# STEP_MOTOR_DRIVER_2.net
KiCad netlist of a schematic drawn in Altium Designer
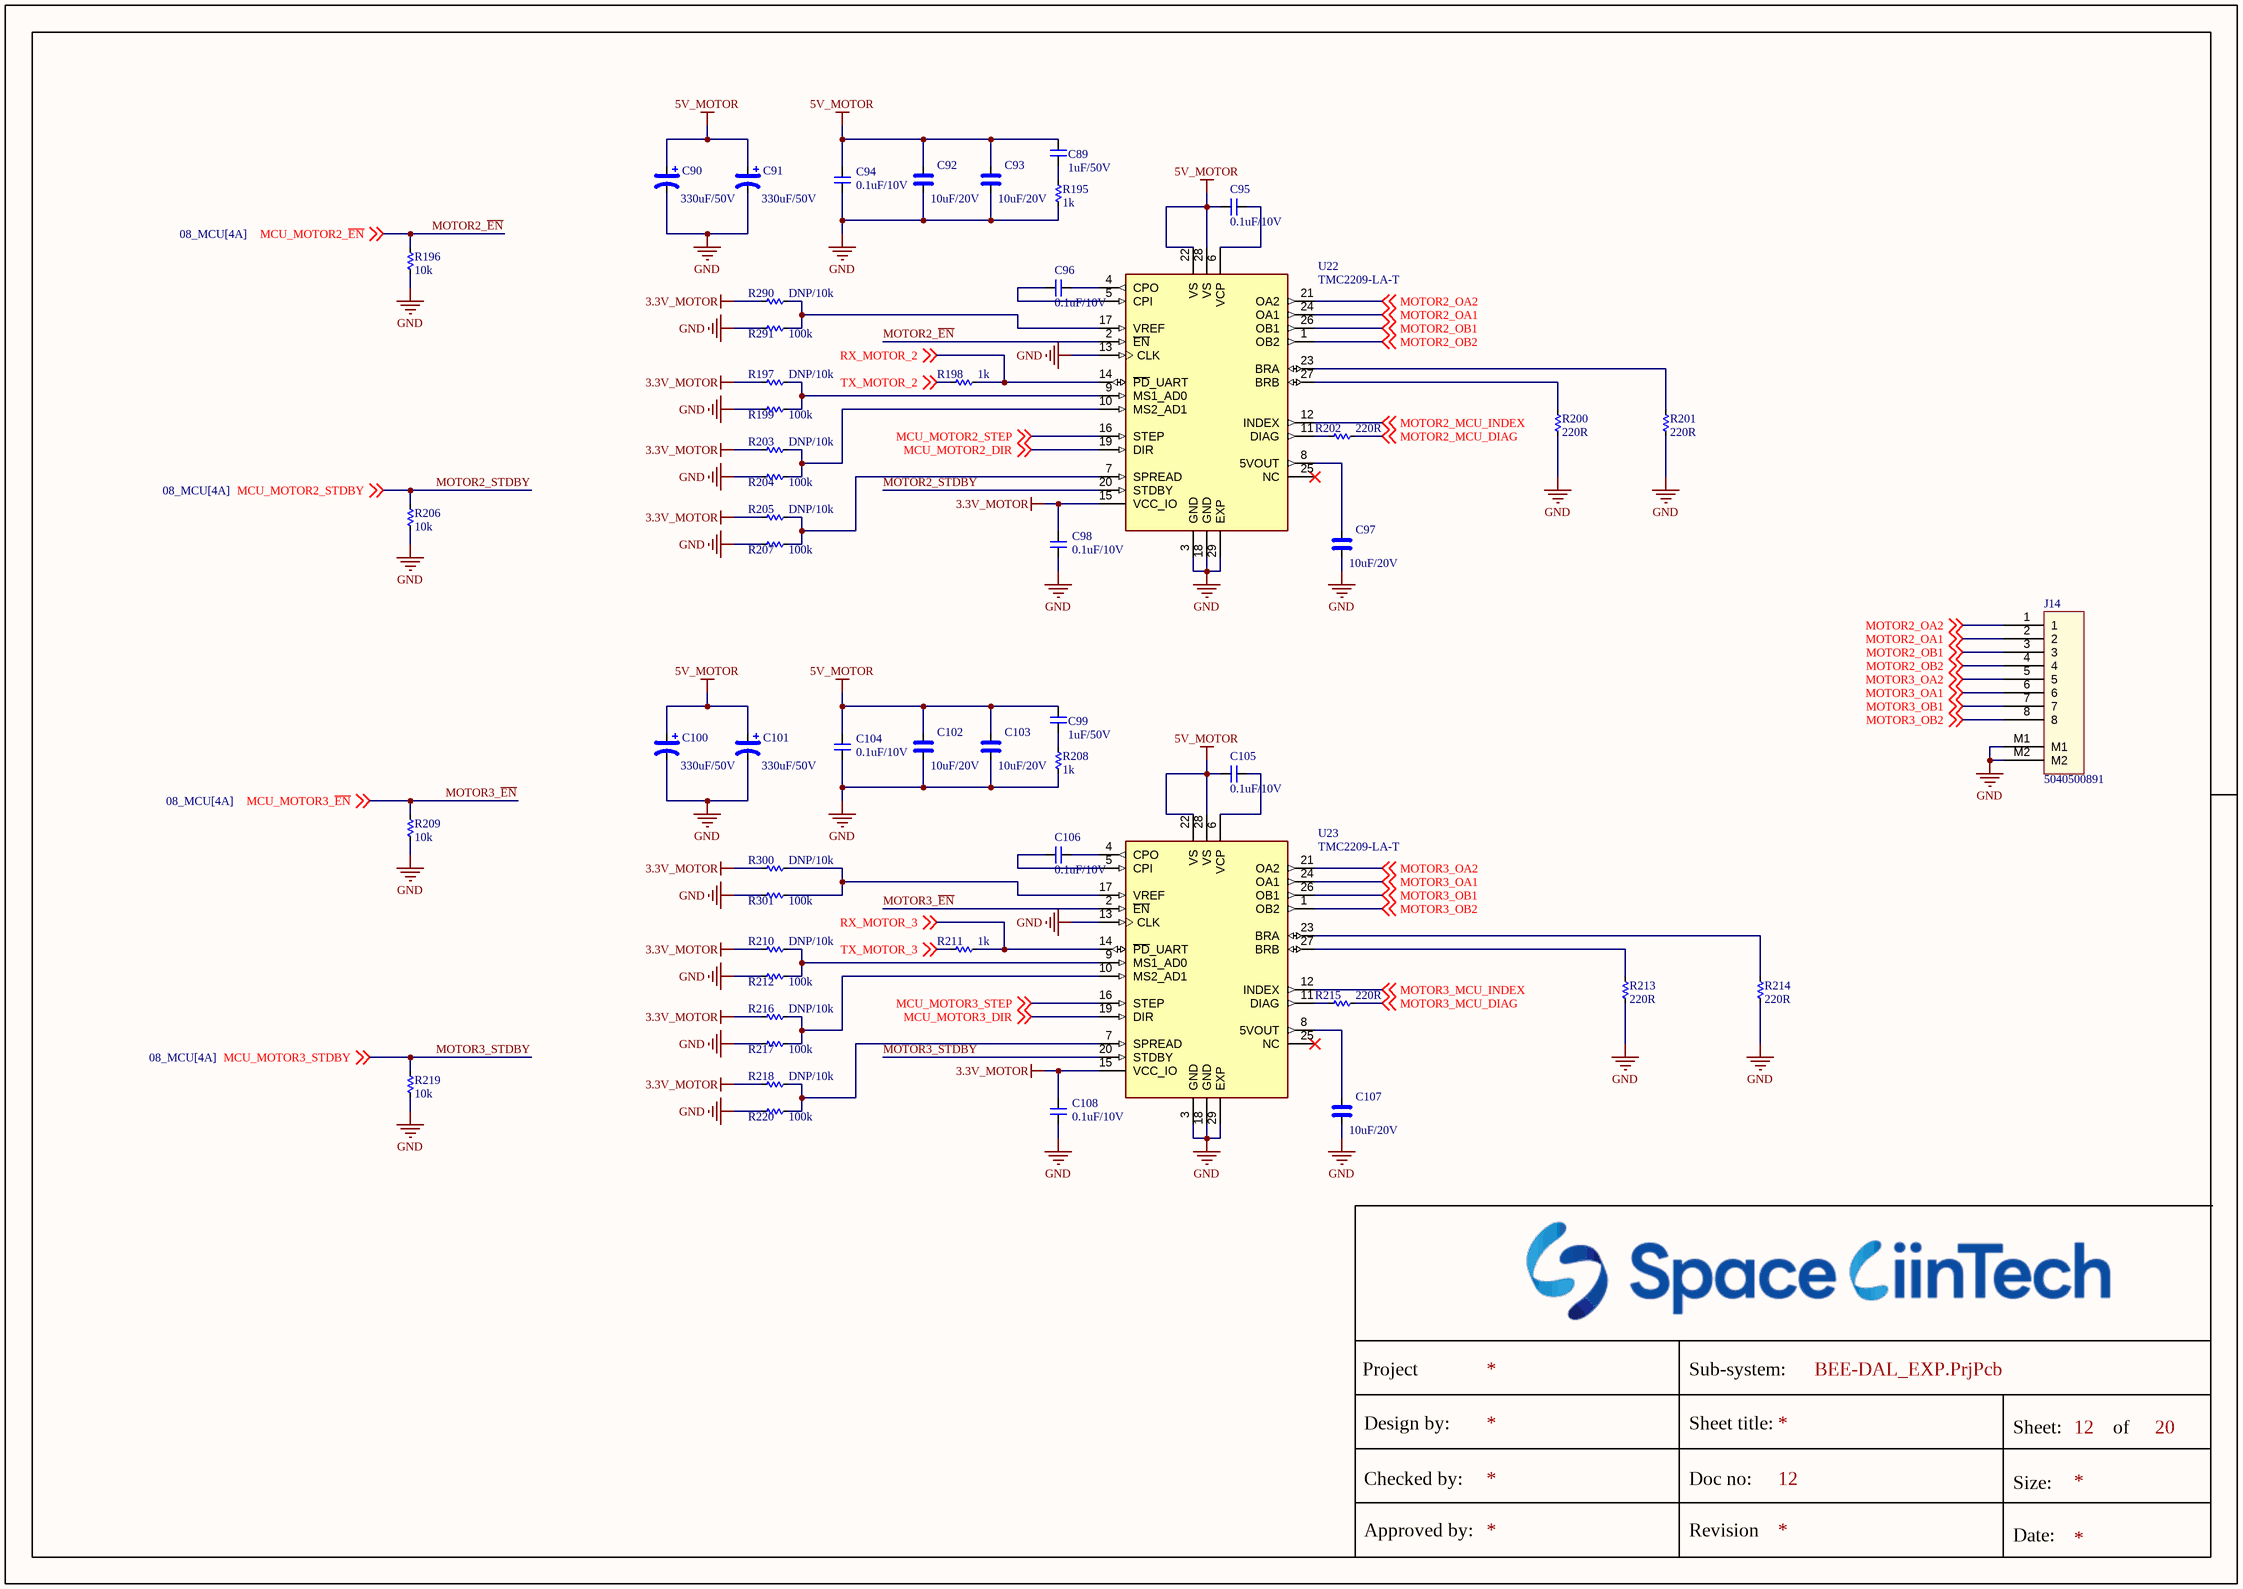
[diagram p0: STEP_MOTOR_DRIVER_2.SchDoc]

(export (version "E")
  (design (tool "Eeschema 10.0.6"))
  (components
    (comp (ref "C89")
      (value "1uF/50V")
      (footprint "CAP_C_1005X50_L")
      (description "CAP")
      (libsource (lib "LABLIB") (part "_CAP_C_2"))
    )
    (comp (ref "C90")
      (value "330uF/50V")
      (footprint "CAP_MP_3216X180")
      (description "CAP Polarization High Value")
      (libsource (lib "LABLIB") (part "_CAP_Pola_High_2"))
    )
    (comp (ref "C91")
      (value "330uF/50V")
      (footprint "CAP_MP_3216X180")
      (description "CAP Polarization High Value")
      (libsource (lib "LABLIB") (part "_CAP_Pola_High_2"))
    )
    (comp (ref "C92")
      (value "10uF/20V")
      (footprint "CAP_C_2012X110")
      (description "CAP High Value")
      (libsource (lib "LABLIB") (part "_CAP_C_High_2"))
    )
    (comp (ref "C93")
      (value "10uF/20V")
      (footprint "CAP_C_2012X110")
      (description "CAP High Value")
      (libsource (lib "LABLIB") (part "_CAP_C_High_2"))
    )
    (comp (ref "C94")
      (value "0.1uF/10V")
      (footprint "CAP_C_1005X50_L")
      (description "CAP")
      (libsource (lib "LABLIB") (part "_CAP_C_2"))
    )
    (comp (ref "C95")
      (value "0.1uF/10V")
      (footprint "CAP_C_1005X50_L")
      (description "CAP")
      (libsource (lib "LABLIB") (part "_CAP_C_2"))
    )
    (comp (ref "C96")
      (value "0.1uF/10V")
      (footprint "CAP_C_1005X50_L")
      (description "CAP")
      (libsource (lib "LABLIB") (part "_CAP_C_2"))
    )
    (comp (ref "C97")
      (value "10uF/20V")
      (footprint "CAP_C_2012X110")
      (description "CAP High Value")
      (libsource (lib "LABLIB") (part "_CAP_C_High_2"))
    )
    (comp (ref "C98")
      (value "0.1uF/10V")
      (footprint "CAP_C_1005X50_L")
      (description "CAP")
      (libsource (lib "LABLIB") (part "_CAP_C_2"))
    )
    (comp (ref "C99")
      (value "1uF/50V")
      (footprint "CAP_C_1005X50_L")
      (description "CAP")
      (libsource (lib "LABLIB") (part "_CAP_C_2"))
    )
    (comp (ref "C100")
      (value "330uF/50V")
      (footprint "CAP_MP_3216X180")
      (description "CAP Polarization High Value")
      (libsource (lib "LABLIB") (part "_CAP_Pola_High_2"))
    )
    (comp (ref "C101")
      (value "330uF/50V")
      (footprint "CAP_MP_3216X180")
      (description "CAP Polarization High Value")
      (libsource (lib "LABLIB") (part "_CAP_Pola_High_2"))
    )
    (comp (ref "C102")
      (value "10uF/20V")
      (footprint "CAP_C_2012X110")
      (description "CAP High Value")
      (libsource (lib "LABLIB") (part "_CAP_C_High_2"))
    )
    (comp (ref "C103")
      (value "10uF/20V")
      (footprint "CAP_C_2012X110")
      (description "CAP High Value")
      (libsource (lib "LABLIB") (part "_CAP_C_High_2"))
    )
    (comp (ref "C104")
      (value "0.1uF/10V")
      (footprint "CAP_C_1005X50_L")
      (description "CAP")
      (libsource (lib "LABLIB") (part "_CAP_C_2"))
    )
    (comp (ref "C105")
      (value "0.1uF/10V")
      (footprint "CAP_C_1005X50_L")
      (description "CAP")
      (libsource (lib "LABLIB") (part "_CAP_C_2"))
    )
    (comp (ref "C106")
      (value "0.1uF/10V")
      (footprint "CAP_C_1005X50_L")
      (description "CAP")
      (libsource (lib "LABLIB") (part "_CAP_C_2"))
    )
    (comp (ref "C107")
      (value "10uF/20V")
      (footprint "CAP_C_2012X110")
      (description "CAP High Value")
      (libsource (lib "LABLIB") (part "_CAP_C_High_2"))
    )
    (comp (ref "C108")
      (value "0.1uF/10V")
      (footprint "CAP_C_1005X50_L")
      (description "CAP")
      (libsource (lib "LABLIB") (part "_CAP_C_2"))
    )
    (comp (ref "J14")
      (value "5040500891")
      (footprint "MOLEX_5040500891")
      (libsource (lib "LABLIB") (part "Header 8x1_2M"))
    )
    (comp (ref "R195")
      (value "1k")
      (footprint "RES_C_1005X40")
      (description "RES")
      (libsource (lib "LABLIB") (part "_RES_B_2"))
    )
    (comp (ref "R196")
      (value "10k")
      (footprint "RES_C_1005X40")
      (description "RES")
      (libsource (lib "LABLIB") (part "_RES_B_2"))
    )
    (comp (ref "R197")
      (value "DNP/10k")
      (footprint "RES_C_1005X40")
      (description "RES")
      (libsource (lib "LABLIB") (part "_RES_B_2"))
    )
    (comp (ref "R198")
      (value "1k")
      (footprint "RES_C_1005X40")
      (description "RES")
      (libsource (lib "LABLIB") (part "_RES_B_2"))
    )
    (comp (ref "R199")
      (value "100k")
      (footprint "RES_C_1005X40")
      (description "RES")
      (libsource (lib "LABLIB") (part "_RES_B_2"))
    )
    (comp (ref "R200")
      (value "220R")
      (footprint "RES_C_1005X40")
      (description "RES")
      (libsource (lib "LABLIB") (part "_RES_B_2"))
    )
    (comp (ref "R201")
      (value "220R")
      (footprint "RES_C_1005X40")
      (description "RES")
      (libsource (lib "LABLIB") (part "_RES_B_2"))
    )
    (comp (ref "R202")
      (value "220R")
      (footprint "RES_C_1005X40")
      (description "RES")
      (libsource (lib "LABLIB") (part "_RES_B_2"))
    )
    (comp (ref "R203")
      (value "DNP/10k")
      (footprint "RES_C_1005X40")
      (description "RES")
      (libsource (lib "LABLIB") (part "_RES_B_2"))
    )
    (comp (ref "R204")
      (value "100k")
      (footprint "RES_C_1005X40")
      (description "RES")
      (libsource (lib "LABLIB") (part "_RES_B_2"))
    )
    (comp (ref "R205")
      (value "DNP/10k")
      (footprint "RES_C_1005X40")
      (description "RES")
      (libsource (lib "LABLIB") (part "_RES_B_2"))
    )
    (comp (ref "R206")
      (value "10k")
      (footprint "RES_C_1005X40")
      (description "RES")
      (libsource (lib "LABLIB") (part "_RES_B_2"))
    )
    (comp (ref "R207")
      (value "100k")
      (footprint "RES_C_1005X40")
      (description "RES")
      (libsource (lib "LABLIB") (part "_RES_B_2"))
    )
    (comp (ref "R208")
      (value "1k")
      (footprint "RES_C_1005X40")
      (description "RES")
      (libsource (lib "LABLIB") (part "_RES_B_2"))
    )
    (comp (ref "R209")
      (value "10k")
      (footprint "RES_C_1005X40")
      (description "RES")
      (libsource (lib "LABLIB") (part "_RES_B_2"))
    )
    (comp (ref "R210")
      (value "DNP/10k")
      (footprint "RES_C_1005X40")
      (description "RES")
      (libsource (lib "LABLIB") (part "_RES_B_2"))
    )
    (comp (ref "R211")
      (value "1k")
      (footprint "RES_C_1005X40")
      (description "RES")
      (libsource (lib "LABLIB") (part "_RES_B_2"))
    )
    (comp (ref "R212")
      (value "100k")
      (footprint "RES_C_1005X40")
      (description "RES")
      (libsource (lib "LABLIB") (part "_RES_B_2"))
    )
    (comp (ref "R213")
      (value "220R")
      (footprint "RES_C_1005X40")
      (description "RES")
      (libsource (lib "LABLIB") (part "_RES_B_2"))
    )
    (comp (ref "R214")
      (value "220R")
      (footprint "RES_C_1005X40")
      (description "RES")
      (libsource (lib "LABLIB") (part "_RES_B_2"))
    )
    (comp (ref "R215")
      (value "220R")
      (footprint "RES_C_1005X40")
      (description "RES")
      (libsource (lib "LABLIB") (part "_RES_B_2"))
    )
    (comp (ref "R216")
      (value "DNP/10k")
      (footprint "RES_C_1005X40")
      (description "RES")
      (libsource (lib "LABLIB") (part "_RES_B_2"))
    )
    (comp (ref "R217")
      (value "100k")
      (footprint "RES_C_1005X40")
      (description "RES")
      (libsource (lib "LABLIB") (part "_RES_B_2"))
    )
    (comp (ref "R218")
      (value "DNP/10k")
      (footprint "RES_C_1005X40")
      (description "RES")
      (libsource (lib "LABLIB") (part "_RES_B_2"))
    )
    (comp (ref "R219")
      (value "10k")
      (footprint "RES_C_1005X40")
      (description "RES")
      (libsource (lib "LABLIB") (part "_RES_B_2"))
    )
    (comp (ref "R220")
      (value "100k")
      (footprint "RES_C_1005X40")
      (description "RES")
      (libsource (lib "LABLIB") (part "_RES_B_2"))
    )
    (comp (ref "R290")
      (value "DNP/10k")
      (footprint "RES_C_1005X40")
      (description "RES")
      (libsource (lib "LABLIB") (part "_RES_B_2"))
    )
    (comp (ref "R291")
      (value "100k")
      (footprint "RES_C_1005X40")
      (description "RES")
      (libsource (lib "LABLIB") (part "_RES_B_2"))
    )
    (comp (ref "R300")
      (value "DNP/10k")
      (footprint "RES_C_1005X40")
      (description "RES")
      (libsource (lib "LABLIB") (part "_RES_B_2"))
    )
    (comp (ref "R301")
      (value "100k")
      (footprint "RES_C_1005X40")
      (description "RES")
      (libsource (lib "LABLIB") (part "_RES_B_2"))
    )
    (comp (ref "U22")
      (value "TMC2209-LA-T")
      (footprint "QFN50P500X500X90-29N")
      (description "Bipolar Motor Driver Power MOSFET Step/Direction, UART 28-QFN (5x5)")
      (fields (field (name "MF") "Trinamic Motion Control GmbH"))
      (libsource (lib "BEE-DAL_EXP_sche") (part "TMC2209-LA-T"))
    )
    (comp (ref "U23")
      (value "TMC2209-LA-T")
      (footprint "QFN50P500X500X90-29N")
      (description "Bipolar Motor Driver Power MOSFET Step/Direction, UART 28-QFN (5x5)")
      (fields (field (name "MF") "Trinamic Motion Control GmbH"))
      (libsource (lib "BEE-DAL_EXP_sche") (part "TMC2209-LA-T"))
    )
  )
  (nets
    (net (code "1") (name "3.3V_MOTOR") (class "Default")
      (node (ref "C108") (pin "2") (pinfunction "2_2") (pintype "passive"))
      (node (ref "C98") (pin "2") (pinfunction "2_2") (pintype "passive"))
      (node (ref "R197") (pin "2") (pinfunction "2_2") (pintype "passive"))
      (node (ref "R203") (pin "2") (pinfunction "2_2") (pintype "passive"))
      (node (ref "R205") (pin "2") (pinfunction "2_2") (pintype "passive"))
      (node (ref "R210") (pin "2") (pinfunction "2_2") (pintype "passive"))
      (node (ref "R216") (pin "2") (pinfunction "2_2") (pintype "passive"))
      (node (ref "R218") (pin "2") (pinfunction "2_2") (pintype "passive"))
      (node (ref "R290") (pin "2") (pinfunction "2_2") (pintype "passive"))
      (node (ref "R300") (pin "2") (pinfunction "2_2") (pintype "passive"))
      (node (ref "U22") (pin "15") (pinfunction "VCC_IO_15") (pintype "power_in"))
      (node (ref "U23") (pin "15") (pinfunction "VCC_IO_15") (pintype "power_in"))
    )
    (net (code "2") (name "5V_MOTOR") (class "Default")
      (node (ref "C100") (pin "1") (pinfunction "1_1") (pintype "passive"))
      (node (ref "C101") (pin "1") (pinfunction "1_1") (pintype "passive"))
      (node (ref "C102") (pin "1") (pinfunction "1_1") (pintype "passive"))
      (node (ref "C103") (pin "1") (pinfunction "1_1") (pintype "passive"))
      (node (ref "C104") (pin "2") (pinfunction "2_2") (pintype "passive"))
      (node (ref "C105") (pin "2") (pinfunction "2_2") (pintype "passive"))
      (node (ref "C89") (pin "2") (pinfunction "2_2") (pintype "passive"))
      (node (ref "C90") (pin "1") (pinfunction "1_1") (pintype "passive"))
      (node (ref "C91") (pin "1") (pinfunction "1_1") (pintype "passive"))
      (node (ref "C92") (pin "1") (pinfunction "1_1") (pintype "passive"))
      (node (ref "C93") (pin "1") (pinfunction "1_1") (pintype "passive"))
      (node (ref "C94") (pin "2") (pinfunction "2_2") (pintype "passive"))
      (node (ref "C95") (pin "2") (pinfunction "2_2") (pintype "passive"))
      (node (ref "C99") (pin "2") (pinfunction "2_2") (pintype "passive"))
      (node (ref "U22") (pin "22") (pinfunction "VS_22") (pintype "power_in"))
      (node (ref "U22") (pin "28") (pinfunction "VS_28") (pintype "power_in"))
      (node (ref "U23") (pin "22") (pinfunction "VS_22") (pintype "power_in"))
      (node (ref "U23") (pin "28") (pinfunction "VS_28") (pintype "power_in"))
    )
    (net (code "3") (name "GND") (class "Default")
      (node (ref "C100") (pin "2") (pinfunction "2_2") (pintype "passive"))
      (node (ref "C101") (pin "2") (pinfunction "2_2") (pintype "passive"))
      (node (ref "C102") (pin "2") (pinfunction "2_2") (pintype "passive"))
      (node (ref "C103") (pin "2") (pinfunction "2_2") (pintype "passive"))
      (node (ref "C104") (pin "1") (pinfunction "1_1") (pintype "passive"))
      (node (ref "C107") (pin "2") (pinfunction "2_2") (pintype "passive"))
      (node (ref "C108") (pin "1") (pinfunction "1_1") (pintype "passive"))
      (node (ref "C90") (pin "2") (pinfunction "2_2") (pintype "passive"))
      (node (ref "C91") (pin "2") (pinfunction "2_2") (pintype "passive"))
      (node (ref "C92") (pin "2") (pinfunction "2_2") (pintype "passive"))
      (node (ref "C93") (pin "2") (pinfunction "2_2") (pintype "passive"))
      (node (ref "C94") (pin "1") (pinfunction "1_1") (pintype "passive"))
      (node (ref "C97") (pin "2") (pinfunction "2_2") (pintype "passive"))
      (node (ref "C98") (pin "1") (pinfunction "1_1") (pintype "passive"))
      (node (ref "J14") (pin "M1") (pinfunction "M1_M1") (pintype "passive"))
      (node (ref "J14") (pin "M2") (pinfunction "M2_M2") (pintype "passive"))
      (node (ref "R195") (pin "1") (pinfunction "1_1") (pintype "passive"))
      (node (ref "R196") (pin "1") (pinfunction "1_1") (pintype "passive"))
      (node (ref "R199") (pin "2") (pinfunction "2_2") (pintype "passive"))
      (node (ref "R200") (pin "2") (pinfunction "2_2") (pintype "passive"))
      (node (ref "R201") (pin "2") (pinfunction "2_2") (pintype "passive"))
      (node (ref "R204") (pin "2") (pinfunction "2_2") (pintype "passive"))
      (node (ref "R206") (pin "1") (pinfunction "1_1") (pintype "passive"))
      (node (ref "R207") (pin "2") (pinfunction "2_2") (pintype "passive"))
      (node (ref "R208") (pin "1") (pinfunction "1_1") (pintype "passive"))
      (node (ref "R209") (pin "1") (pinfunction "1_1") (pintype "passive"))
      (node (ref "R212") (pin "2") (pinfunction "2_2") (pintype "passive"))
      (node (ref "R213") (pin "2") (pinfunction "2_2") (pintype "passive"))
      (node (ref "R214") (pin "2") (pinfunction "2_2") (pintype "passive"))
      (node (ref "R217") (pin "2") (pinfunction "2_2") (pintype "passive"))
      (node (ref "R219") (pin "1") (pinfunction "1_1") (pintype "passive"))
      (node (ref "R220") (pin "2") (pinfunction "2_2") (pintype "passive"))
      (node (ref "R291") (pin "2") (pinfunction "2_2") (pintype "passive"))
      (node (ref "R301") (pin "2") (pinfunction "2_2") (pintype "passive"))
      (node (ref "U22") (pin "13") (pinfunction "CLK_13") (pintype "input"))
      (node (ref "U22") (pin "18") (pinfunction "GND_18") (pintype "power_in"))
      (node (ref "U22") (pin "29") (pinfunction "EXP_29") (pintype "power_in"))
      (node (ref "U22") (pin "3") (pinfunction "GND_3") (pintype "power_in"))
      (node (ref "U23") (pin "13") (pinfunction "CLK_13") (pintype "input"))
      (node (ref "U23") (pin "18") (pinfunction "GND_18") (pintype "power_in"))
      (node (ref "U23") (pin "29") (pinfunction "EXP_29") (pintype "power_in"))
      (node (ref "U23") (pin "3") (pinfunction "GND_3") (pintype "power_in"))
    )
    (net (code "4") (name "MCU_MOTOR2_DIR") (class "Default")
      (node (ref "U22") (pin "19") (pinfunction "DIR_19") (pintype "input"))
    )
    (net (code "5") (name "MCU_MOTOR2_STDBY") (class "Default")
      (node (ref "R206") (pin "2") (pinfunction "2_2") (pintype "passive"))
      (node (ref "U22") (pin "20") (pinfunction "STDBY_20") (pintype "input"))
    )
    (net (code "6") (name "MCU_MOTOR2_STEP") (class "Default")
      (node (ref "U22") (pin "16") (pinfunction "STEP_16") (pintype "input"))
    )
    (net (code "7") (name "MCU_MOTOR2_~{EN}") (class "Default")
      (node (ref "R196") (pin "2") (pinfunction "2_2") (pintype "passive"))
      (node (ref "U22") (pin "2") (pinfunction "~{EN}_2") (pintype "input"))
    )
    (net (code "8") (name "MCU_MOTOR3_DIR") (class "Default")
      (node (ref "U23") (pin "19") (pinfunction "DIR_19") (pintype "input"))
    )
    (net (code "9") (name "MCU_MOTOR3_STDBY") (class "Default")
      (node (ref "R219") (pin "2") (pinfunction "2_2") (pintype "passive"))
      (node (ref "U23") (pin "20") (pinfunction "STDBY_20") (pintype "input"))
    )
    (net (code "10") (name "MCU_MOTOR3_STEP") (class "Default")
      (node (ref "U23") (pin "16") (pinfunction "STEP_16") (pintype "input"))
    )
    (net (code "11") (name "MCU_MOTOR3_~{EN}") (class "Default")
      (node (ref "R209") (pin "2") (pinfunction "2_2") (pintype "passive"))
      (node (ref "U23") (pin "2") (pinfunction "~{EN}_2") (pintype "input"))
    )
    (net (code "12") (name "MOTOR2_MCU_DIAG") (class "Default")
      (node (ref "R202") (pin "2") (pinfunction "2_2") (pintype "passive"))
    )
    (net (code "13") (name "MOTOR2_MCU_INDEX") (class "Default")
      (node (ref "U22") (pin "12") (pinfunction "INDEX_12") (pintype "output"))
    )
    (net (code "14") (name "MOTOR2_OA1") (class "Default")
      (node (ref "J14") (pin "2") (pinfunction "2_2") (pintype "passive"))
      (node (ref "U22") (pin "24") (pinfunction "OA1_24") (pintype "output"))
    )
    (net (code "15") (name "MOTOR2_OA2") (class "Default")
      (node (ref "J14") (pin "1") (pinfunction "1_1") (pintype "passive"))
      (node (ref "U22") (pin "21") (pinfunction "OA2_21") (pintype "output"))
    )
    (net (code "16") (name "MOTOR2_OB1") (class "Default")
      (node (ref "J14") (pin "3") (pinfunction "3_3") (pintype "passive"))
      (node (ref "U22") (pin "26") (pinfunction "OB1_26") (pintype "output"))
    )
    (net (code "17") (name "MOTOR2_OB2") (class "Default")
      (node (ref "J14") (pin "4") (pinfunction "4_4") (pintype "passive"))
      (node (ref "U22") (pin "1") (pinfunction "OB2_1") (pintype "output"))
    )
    (net (code "18") (name "MOTOR3_MCU_DIAG") (class "Default")
      (node (ref "R215") (pin "2") (pinfunction "2_2") (pintype "passive"))
    )
    (net (code "19") (name "MOTOR3_MCU_INDEX") (class "Default")
      (node (ref "U23") (pin "12") (pinfunction "INDEX_12") (pintype "output"))
    )
    (net (code "20") (name "MOTOR3_OA1") (class "Default")
      (node (ref "J14") (pin "6") (pinfunction "6_6") (pintype "passive"))
      (node (ref "U23") (pin "24") (pinfunction "OA1_24") (pintype "output"))
    )
    (net (code "21") (name "MOTOR3_OA2") (class "Default")
      (node (ref "J14") (pin "5") (pinfunction "5_5") (pintype "passive"))
      (node (ref "U23") (pin "21") (pinfunction "OA2_21") (pintype "output"))
    )
    (net (code "22") (name "MOTOR3_OB1") (class "Default")
      (node (ref "J14") (pin "7") (pinfunction "7_7") (pintype "passive"))
      (node (ref "U23") (pin "26") (pinfunction "OB1_26") (pintype "output"))
    )
    (net (code "23") (name "MOTOR3_OB2") (class "Default")
      (node (ref "J14") (pin "8") (pinfunction "8_8") (pintype "passive"))
      (node (ref "U23") (pin "1") (pinfunction "OB2_1") (pintype "output"))
    )
    (net (code "24") (name "Net-(C89-Pad1)") (class "Default")
      (node (ref "C89") (pin "1") (pinfunction "1_1") (pintype "passive"))
      (node (ref "R195") (pin "2") (pinfunction "2_2") (pintype "passive"))
    )
    (net (code "25") (name "Net-(C99-Pad1)") (class "Default")
      (node (ref "C99") (pin "1") (pinfunction "1_1") (pintype "passive"))
      (node (ref "R208") (pin "2") (pinfunction "2_2") (pintype "passive"))
    )
    (net (code "26") (name "Net-(U22-5VOUT)") (class "Default")
      (node (ref "C97") (pin "1") (pinfunction "1_1") (pintype "passive"))
      (node (ref "U22") (pin "8") (pinfunction "5VOUT_8") (pintype "output"))
    )
    (net (code "27") (name "Net-(U22-BRA)") (class "Default")
      (node (ref "R201") (pin "1") (pinfunction "1_1") (pintype "passive"))
      (node (ref "U22") (pin "23") (pinfunction "BRA_23") (pintype "bidirectional"))
    )
    (net (code "28") (name "Net-(U22-BRB)") (class "Default")
      (node (ref "R200") (pin "1") (pinfunction "1_1") (pintype "passive"))
      (node (ref "U22") (pin "27") (pinfunction "BRB_27") (pintype "bidirectional"))
    )
    (net (code "29") (name "Net-(U22-CPI)") (class "Default")
      (node (ref "C96") (pin "2") (pinfunction "2_2") (pintype "passive"))
      (node (ref "U22") (pin "5") (pinfunction "CPI_5") (pintype "input"))
    )
    (net (code "30") (name "Net-(U22-CPO)") (class "Default")
      (node (ref "C96") (pin "1") (pinfunction "1_1") (pintype "passive"))
      (node (ref "U22") (pin "4") (pinfunction "CPO_4") (pintype "output"))
    )
    (net (code "31") (name "Net-(U22-DIAG)") (class "Default")
      (node (ref "R202") (pin "1") (pinfunction "1_1") (pintype "passive"))
      (node (ref "U22") (pin "11") (pinfunction "DIAG_11") (pintype "output"))
    )
    (net (code "32") (name "Net-(U22-MS1_AD0)") (class "Default")
      (node (ref "R197") (pin "1") (pinfunction "1_1") (pintype "passive"))
      (node (ref "R199") (pin "1") (pinfunction "1_1") (pintype "passive"))
      (node (ref "U22") (pin "9") (pinfunction "MS1_AD0_9") (pintype "input"))
    )
    (net (code "33") (name "Net-(U22-MS2_AD1)") (class "Default")
      (node (ref "R203") (pin "1") (pinfunction "1_1") (pintype "passive"))
      (node (ref "R204") (pin "1") (pinfunction "1_1") (pintype "passive"))
      (node (ref "U22") (pin "10") (pinfunction "MS2_AD1_10") (pintype "input"))
    )
    (net (code "34") (name "Net-(U22-SPREAD)") (class "Default")
      (node (ref "R205") (pin "1") (pinfunction "1_1") (pintype "passive"))
      (node (ref "R207") (pin "1") (pinfunction "1_1") (pintype "passive"))
      (node (ref "U22") (pin "7") (pinfunction "SPREAD_7") (pintype "input"))
    )
    (net (code "35") (name "Net-(U22-VCP)") (class "Default")
      (node (ref "C95") (pin "1") (pinfunction "1_1") (pintype "passive"))
      (node (ref "U22") (pin "6") (pinfunction "VCP_6") (pintype "power_in"))
    )
    (net (code "36") (name "Net-(U22-VREF)") (class "Default")
      (node (ref "R290") (pin "1") (pinfunction "1_1") (pintype "passive"))
      (node (ref "R291") (pin "1") (pinfunction "1_1") (pintype "passive"))
      (node (ref "U22") (pin "17") (pinfunction "VREF_17") (pintype "input"))
    )
    (net (code "37") (name "Net-(U23-5VOUT)") (class "Default")
      (node (ref "C107") (pin "1") (pinfunction "1_1") (pintype "passive"))
      (node (ref "U23") (pin "8") (pinfunction "5VOUT_8") (pintype "output"))
    )
    (net (code "38") (name "Net-(U23-BRA)") (class "Default")
      (node (ref "R214") (pin "1") (pinfunction "1_1") (pintype "passive"))
      (node (ref "U23") (pin "23") (pinfunction "BRA_23") (pintype "bidirectional"))
    )
    (net (code "39") (name "Net-(U23-BRB)") (class "Default")
      (node (ref "R213") (pin "1") (pinfunction "1_1") (pintype "passive"))
      (node (ref "U23") (pin "27") (pinfunction "BRB_27") (pintype "bidirectional"))
    )
    (net (code "40") (name "Net-(U23-CPI)") (class "Default")
      (node (ref "C106") (pin "2") (pinfunction "2_2") (pintype "passive"))
      (node (ref "U23") (pin "5") (pinfunction "CPI_5") (pintype "input"))
    )
    (net (code "41") (name "Net-(U23-CPO)") (class "Default")
      (node (ref "C106") (pin "1") (pinfunction "1_1") (pintype "passive"))
      (node (ref "U23") (pin "4") (pinfunction "CPO_4") (pintype "output"))
    )
    (net (code "42") (name "Net-(U23-DIAG)") (class "Default")
      (node (ref "R215") (pin "1") (pinfunction "1_1") (pintype "passive"))
      (node (ref "U23") (pin "11") (pinfunction "DIAG_11") (pintype "output"))
    )
    (net (code "43") (name "Net-(U23-MS1_AD0)") (class "Default")
      (node (ref "R210") (pin "1") (pinfunction "1_1") (pintype "passive"))
      (node (ref "R212") (pin "1") (pinfunction "1_1") (pintype "passive"))
      (node (ref "U23") (pin "9") (pinfunction "MS1_AD0_9") (pintype "input"))
    )
    (net (code "44") (name "Net-(U23-MS2_AD1)") (class "Default")
      (node (ref "R216") (pin "1") (pinfunction "1_1") (pintype "passive"))
      (node (ref "R217") (pin "1") (pinfunction "1_1") (pintype "passive"))
      (node (ref "U23") (pin "10") (pinfunction "MS2_AD1_10") (pintype "input"))
    )
    (net (code "45") (name "Net-(U23-SPREAD)") (class "Default")
      (node (ref "R218") (pin "1") (pinfunction "1_1") (pintype "passive"))
      (node (ref "R220") (pin "1") (pinfunction "1_1") (pintype "passive"))
      (node (ref "U23") (pin "7") (pinfunction "SPREAD_7") (pintype "input"))
    )
    (net (code "46") (name "Net-(U23-VCP)") (class "Default")
      (node (ref "C105") (pin "1") (pinfunction "1_1") (pintype "passive"))
      (node (ref "U23") (pin "6") (pinfunction "VCP_6") (pintype "power_in"))
    )
    (net (code "47") (name "Net-(U23-VREF)") (class "Default")
      (node (ref "R300") (pin "1") (pinfunction "1_1") (pintype "passive"))
      (node (ref "R301") (pin "1") (pinfunction "1_1") (pintype "passive"))
      (node (ref "U23") (pin "17") (pinfunction "VREF_17") (pintype "input"))
    )
    (net (code "48") (name "RX_MOTOR_2") (class "Default")
      (node (ref "R198") (pin "2") (pinfunction "2_2") (pintype "passive"))
      (node (ref "U22") (pin "14") (pinfunction "~{PD}_UART_14") (pintype "bidirectional"))
    )
    (net (code "49") (name "RX_MOTOR_3") (class "Default")
      (node (ref "R211") (pin "2") (pinfunction "2_2") (pintype "passive"))
      (node (ref "U23") (pin "14") (pinfunction "~{PD}_UART_14") (pintype "bidirectional"))
    )
    (net (code "50") (name "TX_MOTOR_2") (class "Default")
      (node (ref "R198") (pin "1") (pinfunction "1_1") (pintype "passive"))
    )
    (net (code "51") (name "TX_MOTOR_3") (class "Default")
      (node (ref "R211") (pin "1") (pinfunction "1_1") (pintype "passive"))
    )
    (net (code "52") (name "unconnected-(U22-NC-Pad25)") (class "Default")
      (node (ref "U22") (pin "25") (pinfunction "NC_25") (pintype "passive+no_connect"))
    )
    (net (code "53") (name "unconnected-(U23-NC-Pad25)") (class "Default")
      (node (ref "U23") (pin "25") (pinfunction "NC_25") (pintype "passive+no_connect"))
    )
  )
)
